# adc_chanels.net
KiCad netlist of a schematic drawn in Altium Designer
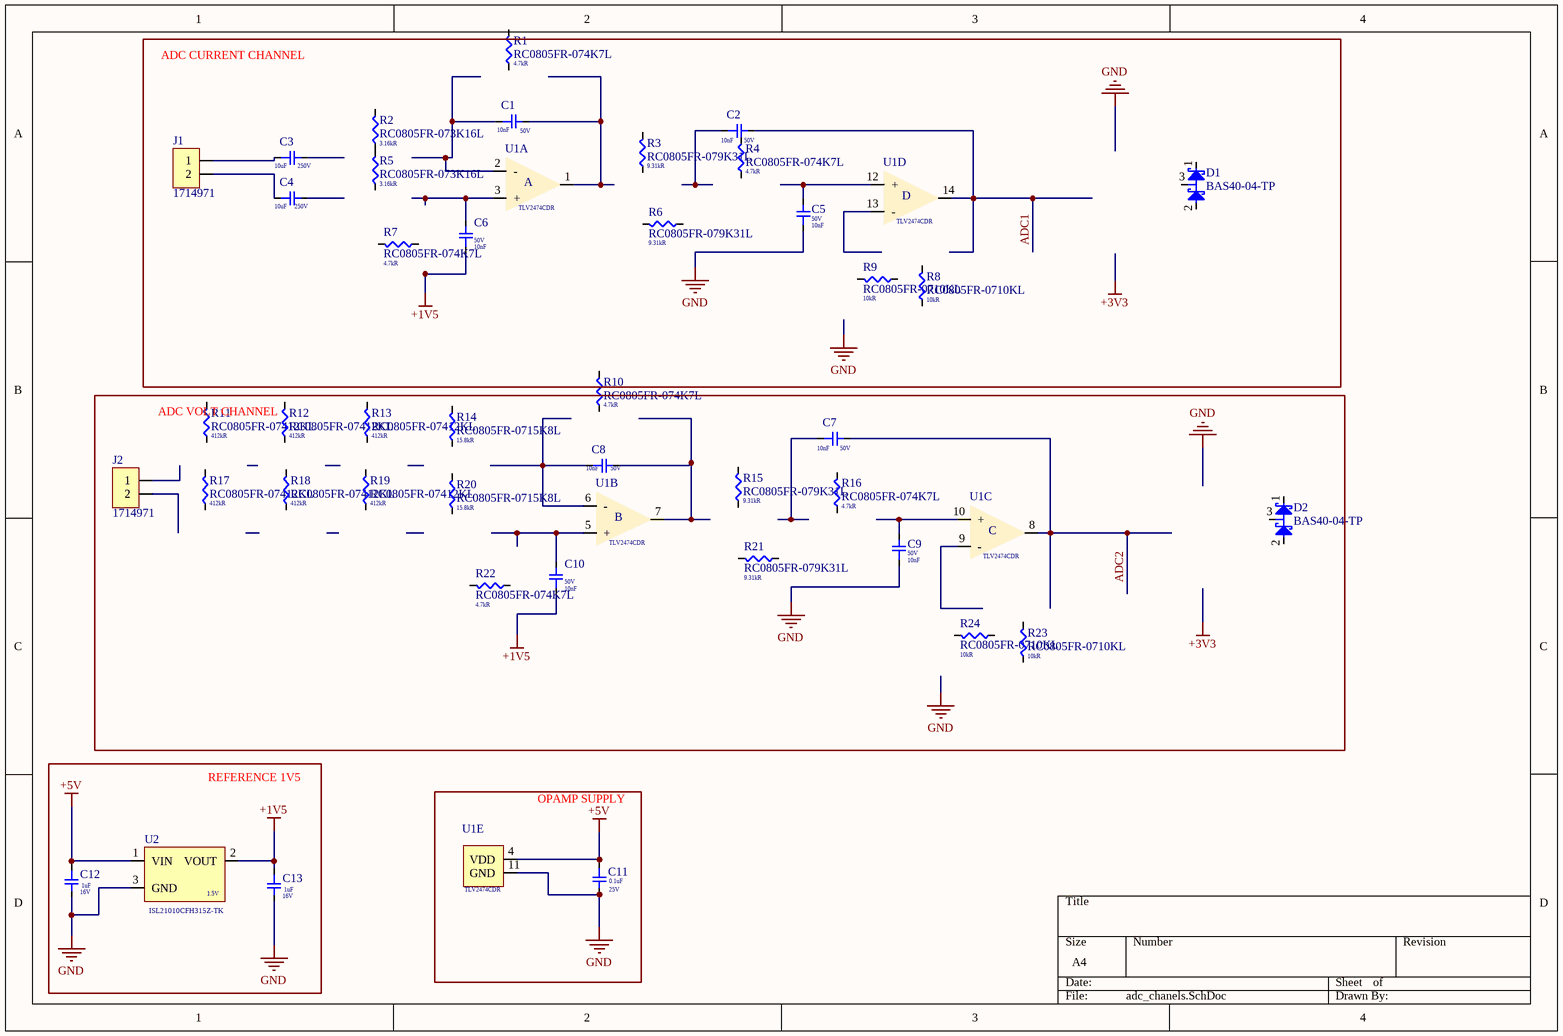
[diagram p0: adc_chanels.SchDoc]

(export (version "E")
  (design (tool "Eeschema 10.0.6"))
  (components
    (comp (ref "C1")
      (value "CAP_GRM2195C1H103FA01D_MURATA")
      (footprint "CAP smd 0805")
      (description "0805 10 nF 50 V ±1% Tolerance C0G SMD Multilayer Ceramic Capacitor")
      (fields
        (field (name "TOLERANCE") "1%")
        (field (name "VOLTAGE") "50V")
        (field (name "CAPACITANCE") "10nF")
      )
      (libsource (lib "Cap") (part "CAP_GRM2195C1H103FA01D_MURATA"))
    )
    (comp (ref "C2")
      (value "CAP_GRM2195C1H103FA01D_MURATA")
      (footprint "CAP smd 0805")
      (description "0805 10 nF 50 V ±1% Tolerance C0G SMD Multilayer Ceramic Capacitor")
      (fields
        (field (name "TOLERANCE") "1%")
        (field (name "VOLTAGE") "50V")
        (field (name "CAPACITANCE") "10nF")
      )
      (libsource (lib "Cap") (part "CAP_GRM2195C1H103FA01D_MURATA"))
    )
    (comp (ref "C3")
      (value "CAP_B32754C2106K000")
      (footprint "Cap 22x36.5x31.5")
      (description "Cap Film 10uF 500V PP 10% (31.5 X 22 X 36.5mm) Dipped Radial 27.5mm 105°C Bulk")
      (fields
        (field (name "TOLERANCE") "10%")
        (field (name "VOLTAGE RATING (AC)") "250V")
        (field (name "CAPACITANCE") "10uF")
      )
      (libsource (lib "Cap") (part "CAP_B32754C2106K000"))
    )
    (comp (ref "C4")
      (value "CAP_B32754C2106K000")
      (footprint "Cap 22x36.5x31.5")
      (description "Cap Film 10uF 500V PP 10% (31.5 X 22 X 36.5mm) Dipped Radial 27.5mm 105°C Bulk")
      (fields
        (field (name "TOLERANCE") "10%")
        (field (name "VOLTAGE RATING (AC)") "250V")
        (field (name "CAPACITANCE") "10uF")
      )
      (libsource (lib "Cap") (part "CAP_B32754C2106K000"))
    )
    (comp (ref "C5")
      (value "CAP_GRM2195C1H103FA01D_MURATA")
      (footprint "CAP smd 0805")
      (description "0805 10 nF 50 V ±1% Tolerance C0G SMD Multilayer Ceramic Capacitor")
      (fields
        (field (name "TOLERANCE") "1%")
        (field (name "VOLTAGE") "50V")
        (field (name "CAPACITANCE") "10nF")
      )
      (libsource (lib "Cap") (part "CAP_GRM2195C1H103FA01D_MURATA"))
    )
    (comp (ref "C6")
      (value "CAP_GRM2195C1H103FA01D_MURATA")
      (footprint "CAP smd 0805")
      (description "0805 10 nF 50 V ±1% Tolerance C0G SMD Multilayer Ceramic Capacitor")
      (fields
        (field (name "TOLERANCE") "1%")
        (field (name "VOLTAGE") "50V")
        (field (name "CAPACITANCE") "10nF")
      )
      (libsource (lib "Cap") (part "CAP_GRM2195C1H103FA01D_MURATA"))
    )
    (comp (ref "C7")
      (value "CAP_GRM2195C1H103FA01D_MURATA")
      (footprint "CAP smd 0805")
      (description "0805 10 nF 50 V ±1% Tolerance C0G SMD Multilayer Ceramic Capacitor")
      (fields
        (field (name "TOLERANCE") "1%")
        (field (name "VOLTAGE") "50V")
        (field (name "CAPACITANCE") "10nF")
      )
      (libsource (lib "Cap") (part "CAP_GRM2195C1H103FA01D_MURATA"))
    )
    (comp (ref "C8")
      (value "CAP_GRM2195C1H103FA01D_MURATA")
      (footprint "CAP smd 0805")
      (description "0805 10 nF 50 V ±1% Tolerance C0G SMD Multilayer Ceramic Capacitor")
      (fields
        (field (name "TOLERANCE") "1%")
        (field (name "VOLTAGE") "50V")
        (field (name "CAPACITANCE") "10nF")
      )
      (libsource (lib "Cap") (part "CAP_GRM2195C1H103FA01D_MURATA"))
    )
    (comp (ref "C9")
      (value "CAP_GRM2195C1H103FA01D_MURATA")
      (footprint "CAP smd 0805")
      (description "0805 10 nF 50 V ±1% Tolerance C0G SMD Multilayer Ceramic Capacitor")
      (fields
        (field (name "TOLERANCE") "1%")
        (field (name "VOLTAGE") "50V")
        (field (name "CAPACITANCE") "10nF")
      )
      (libsource (lib "Cap") (part "CAP_GRM2195C1H103FA01D_MURATA"))
    )
    (comp (ref "C10")
      (value "CAP_GRM2195C1H103FA01D_MURATA")
      (footprint "CAP smd 0805")
      (description "0805 10 nF 50 V ±1% Tolerance C0G SMD Multilayer Ceramic Capacitor")
      (fields
        (field (name "TOLERANCE") "1%")
        (field (name "VOLTAGE") "50V")
        (field (name "CAPACITANCE") "10nF")
      )
      (libsource (lib "Cap") (part "CAP_GRM2195C1H103FA01D_MURATA"))
    )
    (comp (ref "C11")
      (value "CAP_CC0805KRX7R8BB104_YAGEO")
      (footprint "CAP smd 0805")
      (description "CAPACITOR, 0805, 100NF, 25V, REEL 4000")
      (fields
        (field (name "TOLERANCE") "10%")
        (field (name "VOLTAGE RATING") "25V")
        (field (name "CAPACITANCE") "0.1uF")
      )
      (libsource (lib "Cap") (part "CAP_CC0805KRX7R8BB104_YAGEO"))
    )
    (comp (ref "C12")
      (value "CAP_CC0805KKX7R7BB105_YAGEO")
      (footprint "CAP smd 0805")
      (description "YAGEO   CC0805KKX7R7BB105   CERAMIC CAPACITOR, 1UF, 16V, X7R, 10%, 0805")
      (fields
        (field (name "TOLERANCE") "10%")
        (field (name "VOLTAGE RATING") "16V")
        (field (name "CAPACITANCE") "1uF")
      )
      (libsource (lib "Cap") (part "CAP_CC0805KKX7R7BB105_YAGEO"))
    )
    (comp (ref "C13")
      (value "CAP_CC0805KKX7R7BB105_YAGEO")
      (footprint "CAP smd 0805")
      (description "YAGEO   CC0805KKX7R7BB105   CERAMIC CAPACITOR, 1UF, 16V, X7R, 10%, 0805")
      (fields
        (field (name "TOLERANCE") "10%")
        (field (name "VOLTAGE RATING") "16V")
        (field (name "CAPACITANCE") "1uF")
      )
      (libsource (lib "Cap") (part "CAP_CC0805KKX7R7BB105_YAGEO"))
    )
    (comp (ref "D1")
      (value "BAS40-04-TP")
      (footprint "SOT-23")
      (description "DIODE ARRAY SCHOTTKY 40V SOT23")
      (libsource (lib "diode") (part "BAS40-04-TP"))
    )
    (comp (ref "D2")
      (value "BAS40-04-TP")
      (footprint "SOT-23")
      (description "DIODE ARRAY SCHOTTKY 40V SOT23")
      (libsource (lib "diode") (part "BAS40-04-TP"))
    )
    (comp (ref "J1")
      (value "1714971")
      (description "Large Style 2pos 32a 500vac 24-10awg Green Plastic Interlocking Housing 9.5.0mm Pitch")
      (fields (field (name "VOLTAGE") "600V"))
      (libsource (lib "conectors") (part "1714971"))
    )
    (comp (ref "J2")
      (value "1714971")
      (description "Large Style 2pos 32a 500vac 24-10awg Green Plastic Interlocking Housing 9.5.0mm Pitch")
      (fields (field (name "VOLTAGE") "600V"))
      (libsource (lib "conectors") (part "1714971"))
    )
    (comp (ref "R1")
      (value "RC0805FR-074K7L")
      (footprint "res 0805")
      (description "YAGEO - RC0805FR-074K7L - SMD  0805 [2012 Metric], 4.7 kohm,  125 mW")
      (fields (field (name "TOLERANCE") "1%") (field (name "RESISTANCE") "4.7kR"))
      (libsource (lib "res") (part "RC0805FR-074K7L"))
    )
    (comp (ref "R2")
      (value "RC0805FR-073K16L")
      (footprint "res 0805")
      (description "Res Thick Film smd 0805 3.16K Ohm 1% 0.125W(1/8W)")
      (fields (field (name "TOLERANCE") "1%") (field (name "RESISTANCE") "3.16kR"))
      (libsource (lib "res") (part "RC0805FR-073K16L"))
    )
    (comp (ref "R3")
      (value "RC0805FR-079K31L")
      (footprint "res 0805")
      (description "Res Thick Film smd 0805 9.31K Ohm 1% 0.125W(1/8W)")
      (fields (field (name "TOLERANCE") "1%") (field (name "RESISTANCE") "9.31kR"))
      (libsource (lib "res") (part "RC0805FR-079K31L"))
    )
    (comp (ref "R4")
      (value "RC0805FR-074K7L")
      (footprint "res 0805")
      (description "YAGEO - RC0805FR-074K7L - SMD  0805 [2012 Metric], 4.7 kohm,  125 mW")
      (fields (field (name "TOLERANCE") "1%") (field (name "RESISTANCE") "4.7kR"))
      (libsource (lib "res") (part "RC0805FR-074K7L"))
    )
    (comp (ref "R5")
      (value "RC0805FR-073K16L")
      (footprint "res 0805")
      (description "Res Thick Film smd 0805 3.16K Ohm 1% 0.125W(1/8W)")
      (fields (field (name "TOLERANCE") "1%") (field (name "RESISTANCE") "3.16kR"))
      (libsource (lib "res") (part "RC0805FR-073K16L"))
    )
    (comp (ref "R6")
      (value "RC0805FR-079K31L")
      (footprint "res 0805")
      (description "Res Thick Film smd 0805 9.31K Ohm 1% 0.125W(1/8W)")
      (fields (field (name "TOLERANCE") "1%") (field (name "RESISTANCE") "9.31kR"))
      (libsource (lib "res") (part "RC0805FR-079K31L"))
    )
    (comp (ref "R7")
      (value "RC0805FR-074K7L")
      (footprint "res 0805")
      (description "YAGEO - RC0805FR-074K7L - SMD  0805 [2012 Metric], 4.7 kohm,  125 mW")
      (fields (field (name "TOLERANCE") "1%") (field (name "RESISTANCE") "4.7kR"))
      (libsource (lib "res") (part "RC0805FR-074K7L"))
    )
    (comp (ref "R8")
      (value "RC0805FR-0710KL")
      (footprint "res 0805")
      (description "RES SMD  0805 10K OHM 1% 1/8W")
      (fields (field (name "TOLERANCE") "1%") (field (name "RESISTANCE") "10kR"))
      (libsource (lib "res") (part "RC0805FR-0710KL"))
    )
    (comp (ref "R9")
      (value "RC0805FR-0710KL")
      (footprint "res 0805")
      (description "RES SMD  0805 10K OHM 1% 1/8W")
      (fields (field (name "TOLERANCE") "1%") (field (name "RESISTANCE") "10kR"))
      (libsource (lib "res") (part "RC0805FR-0710KL"))
    )
    (comp (ref "R10")
      (value "RC0805FR-074K7L")
      (footprint "res 0805")
      (description "YAGEO - RC0805FR-074K7L - SMD  0805 [2012 Metric], 4.7 kohm,  125 mW")
      (fields (field (name "TOLERANCE") "1%") (field (name "RESISTANCE") "4.7kR"))
      (libsource (lib "res") (part "RC0805FR-074K7L"))
    )
    (comp (ref "R11")
      (value "RC0805FR-07412KL")
      (footprint "res 0805")
      (description "RES SMD 0805 412K OHM 1% 1/8W")
      (fields (field (name "TOLERANCE") "1%") (field (name "RESISTANCE") "412kR"))
      (libsource (lib "res") (part "RC0805FR-07412KL"))
    )
    (comp (ref "R12")
      (value "RC0805FR-07412KL")
      (footprint "res 0805")
      (description "RES SMD 0805 412K OHM 1% 1/8W")
      (fields (field (name "TOLERANCE") "1%") (field (name "RESISTANCE") "412kR"))
      (libsource (lib "res") (part "RC0805FR-07412KL"))
    )
    (comp (ref "R13")
      (value "RC0805FR-07412KL")
      (footprint "res 0805")
      (description "RES SMD 0805 412K OHM 1% 1/8W")
      (fields (field (name "TOLERANCE") "1%") (field (name "RESISTANCE") "412kR"))
      (libsource (lib "res") (part "RC0805FR-07412KL"))
    )
    (comp (ref "R14")
      (value "RC0805FR-0715K8L")
      (footprint "res 0805")
      (description "Res Thick Film smd 0805 15.8K Ohm 1% 0.125W(1/8W)")
      (fields (field (name "TOLERANCE") "1%") (field (name "RESISTANCE") "15.8kR"))
      (libsource (lib "res") (part "RC0805FR-0715K8L"))
    )
    (comp (ref "R15")
      (value "RC0805FR-079K31L")
      (footprint "res 0805")
      (description "Res Thick Film smd 0805 9.31K Ohm 1% 0.125W(1/8W)")
      (fields (field (name "TOLERANCE") "1%") (field (name "RESISTANCE") "9.31kR"))
      (libsource (lib "res") (part "RC0805FR-079K31L"))
    )
    (comp (ref "R16")
      (value "RC0805FR-074K7L")
      (footprint "res 0805")
      (description "YAGEO - RC0805FR-074K7L - SMD  0805 [2012 Metric], 4.7 kohm,  125 mW")
      (fields (field (name "TOLERANCE") "1%") (field (name "RESISTANCE") "4.7kR"))
      (libsource (lib "res") (part "RC0805FR-074K7L"))
    )
    (comp (ref "R17")
      (value "RC0805FR-07412KL")
      (footprint "res 0805")
      (description "RES SMD 0805 412K OHM 1% 1/8W")
      (fields (field (name "TOLERANCE") "1%") (field (name "RESISTANCE") "412kR"))
      (libsource (lib "res") (part "RC0805FR-07412KL"))
    )
    (comp (ref "R18")
      (value "RC0805FR-07412KL")
      (footprint "res 0805")
      (description "RES SMD 0805 412K OHM 1% 1/8W")
      (fields (field (name "TOLERANCE") "1%") (field (name "RESISTANCE") "412kR"))
      (libsource (lib "res") (part "RC0805FR-07412KL"))
    )
    (comp (ref "R19")
      (value "RC0805FR-07412KL")
      (footprint "res 0805")
      (description "RES SMD 0805 412K OHM 1% 1/8W")
      (fields (field (name "TOLERANCE") "1%") (field (name "RESISTANCE") "412kR"))
      (libsource (lib "res") (part "RC0805FR-07412KL"))
    )
    (comp (ref "R20")
      (value "RC0805FR-0715K8L")
      (footprint "res 0805")
      (description "Res Thick Film smd 0805 15.8K Ohm 1% 0.125W(1/8W)")
      (fields (field (name "TOLERANCE") "1%") (field (name "RESISTANCE") "15.8kR"))
      (libsource (lib "res") (part "RC0805FR-0715K8L"))
    )
    (comp (ref "R21")
      (value "RC0805FR-079K31L")
      (footprint "res 0805")
      (description "Res Thick Film smd 0805 9.31K Ohm 1% 0.125W(1/8W)")
      (fields (field (name "TOLERANCE") "1%") (field (name "RESISTANCE") "9.31kR"))
      (libsource (lib "res") (part "RC0805FR-079K31L"))
    )
    (comp (ref "R22")
      (value "RC0805FR-074K7L")
      (footprint "res 0805")
      (description "YAGEO - RC0805FR-074K7L - SMD  0805 [2012 Metric], 4.7 kohm,  125 mW")
      (fields (field (name "TOLERANCE") "1%") (field (name "RESISTANCE") "4.7kR"))
      (libsource (lib "res") (part "RC0805FR-074K7L"))
    )
    (comp (ref "R23")
      (value "RC0805FR-0710KL")
      (footprint "res 0805")
      (description "RES SMD  0805 10K OHM 1% 1/8W")
      (fields (field (name "TOLERANCE") "1%") (field (name "RESISTANCE") "10kR"))
      (libsource (lib "res") (part "RC0805FR-0710KL"))
    )
    (comp (ref "R24")
      (value "RC0805FR-0710KL")
      (footprint "res 0805")
      (description "RES SMD  0805 10K OHM 1% 1/8W")
      (fields (field (name "TOLERANCE") "1%") (field (name "RESISTANCE") "10kR"))
      (libsource (lib "res") (part "RC0805FR-0710KL"))
    )
    (comp (ref "U1")
      (value "TLV2474CDR")
      (description "OP Amp Quad GP R-R I/O ±3V/6V 14-Pin SOIC T/R")
      (libsource (lib "ic") (part "TLV2474CDR"))
    )
    (comp (ref "U2")
      (value "ISL21010CFH315Z-TK")
      (fields
        (field (name "TOLERANCE") "0.2%")
        (field (name "MANUFACTURER PART NUMBER 1") "ISL21010CFH315Z-TK")
        (field (name "REFERENCE VOLTAGE") "1.5V")
      )
      (libsource (lib "ic") (part "ISL21010CFH315Z-TK"))
    )
  )
  (nets
    (net (code "1") (name "+1V5") (class "Default")
      (node (ref "C10") (pin "23") (pinfunction "23_23") (pintype "passive"))
      (node (ref "C13") (pin "23") (pinfunction "23_23") (pintype "passive"))
      (node (ref "C6") (pin "23") (pinfunction "23_23") (pintype "passive"))
      (node (ref "U2") (pin "2") (pinfunction "VOUT_2") (pintype "passive"))
    )
    (net (code "3") (name "+5V") (class "Default")
      (node (ref "C11") (pin "23") (pinfunction "23_23") (pintype "passive"))
      (node (ref "C12") (pin "23") (pinfunction "23_23") (pintype "passive"))
      (node (ref "U1") (pin "4") (pinfunction "VDD_4") (pintype "passive"))
      (node (ref "U2") (pin "1") (pinfunction "VIN_1") (pintype "passive"))
    )
    (net (code "4") (name "/ADC1") (class "Default")
      (node (ref "C2") (pin "22") (pinfunction "22_22") (pintype "passive"))
      (node (ref "U1") (pin "14") (pinfunction "14_14") (pintype "passive"))
    )
    (net (code "5") (name "/ADC2") (class "Default")
      (node (ref "C7") (pin "22") (pinfunction "22_22") (pintype "passive"))
      (node (ref "U1") (pin "8") (pinfunction "1_8") (pintype "passive"))
    )
    (net (code "6") (name "GND") (class "Default")
      (node (ref "C11") (pin "22") (pinfunction "22_22") (pintype "passive"))
      (node (ref "C12") (pin "22") (pinfunction "22_22") (pintype "passive"))
      (node (ref "C13") (pin "22") (pinfunction "22_22") (pintype "passive"))
      (node (ref "C5") (pin "23") (pinfunction "23_23") (pintype "passive"))
      (node (ref "C9") (pin "23") (pinfunction "23_23") (pintype "passive"))
      (node (ref "U1") (pin "11") (pinfunction "GND_11") (pintype "passive"))
      (node (ref "U2") (pin "3") (pinfunction "GND_3") (pintype "passive"))
    )
    (net (code "7") (name "Net-(C1-Pad22)") (class "Default")
      (node (ref "C1") (pin "22") (pinfunction "22_22") (pintype "passive"))
      (node (ref "U1") (pin "1") (pinfunction "1_1") (pintype "passive"))
    )
    (net (code "8") (name "Net-(C3-Pad23)") (class "Default")
      (node (ref "C3") (pin "23") (pinfunction "23_23") (pintype "passive"))
      (node (ref "J1") (pin "1") (pinfunction "1_1") (pintype "passive"))
    )
    (net (code "9") (name "Net-(C4-Pad23)") (class "Default")
      (node (ref "C4") (pin "23") (pinfunction "23_23") (pintype "passive"))
      (node (ref "J1") (pin "2") (pinfunction "2_2") (pintype "passive"))
    )
    (net (code "10") (name "Net-(R2-Pad2)") (class "Default")
      (node (ref "R2") (pin "2") (pinfunction "2_2") (pintype "passive"))
      (node (ref "R5") (pin "1") (pinfunction "1_1") (pintype "passive"))
    )
    (net (code "11") (name "Net-(U1A-+)") (class "Default")
      (node (ref "C6") (pin "22") (pinfunction "22_22") (pintype "passive"))
      (node (ref "U1") (pin "3") (pinfunction "+_3") (pintype "passive"))
    )
    (net (code "12") (name "Net-(U1A--)") (class "Default")
      (node (ref "C1") (pin "23") (pinfunction "23_23") (pintype "passive"))
      (node (ref "U1") (pin "2") (pinfunction "-_2") (pintype "passive"))
    )
    (net (code "13") (name "Net-(U1B-+)") (class "Default")
      (node (ref "C10") (pin "22") (pinfunction "22_22") (pintype "passive"))
      (node (ref "U1") (pin "5") (pinfunction "+_5") (pintype "passive"))
    )
    (net (code "14") (name "Net-(U1B--)") (class "Default")
      (node (ref "C8") (pin "23") (pinfunction "23_23") (pintype "passive"))
      (node (ref "U1") (pin "6") (pinfunction "-_6") (pintype "passive"))
    )
    (net (code "15") (name "Net-(U1B-1)") (class "Default")
      (node (ref "C8") (pin "22") (pinfunction "22_22") (pintype "passive"))
      (node (ref "U1") (pin "7") (pinfunction "1_7") (pintype "passive"))
    )
    (net (code "16") (name "Net-(U1C-+)") (class "Default")
      (node (ref "C9") (pin "22") (pinfunction "22_22") (pintype "passive"))
      (node (ref "U1") (pin "10") (pinfunction "+_10") (pintype "passive"))
    )
    (net (code "17") (name "Net-(U1D-+)") (class "Default")
      (node (ref "C5") (pin "22") (pinfunction "22_22") (pintype "passive"))
      (node (ref "U1") (pin "12") (pinfunction "+_12") (pintype "passive"))
    )
    (net (code "18") (name "unconnected-(C2-Pad23)") (class "Default")
      (node (ref "C2") (pin "23") (pinfunction "23_23") (pintype "passive"))
    )
    (net (code "19") (name "unconnected-(C3-Pad22)") (class "Default")
      (node (ref "C3") (pin "22") (pinfunction "22_22") (pintype "passive"))
    )
    (net (code "20") (name "unconnected-(C4-Pad22)") (class "Default")
      (node (ref "C4") (pin "22") (pinfunction "22_22") (pintype "passive"))
    )
    (net (code "21") (name "unconnected-(C7-Pad23)") (class "Default")
      (node (ref "C7") (pin "23") (pinfunction "23_23") (pintype "passive"))
    )
    (net (code "22") (name "unconnected-(D1-Pad1)") (class "Default")
      (node (ref "D1") (pin "1") (pinfunction "1_1") (pintype "passive"))
    )
    (net (code "23") (name "unconnected-(D1-Pad2)") (class "Default")
      (node (ref "D1") (pin "2") (pinfunction "2_2") (pintype "passive"))
    )
    (net (code "24") (name "unconnected-(D1-Pad3)") (class "Default")
      (node (ref "D1") (pin "3") (pinfunction "3_3") (pintype "passive"))
    )
    (net (code "25") (name "unconnected-(D2-Pad1)") (class "Default")
      (node (ref "D2") (pin "1") (pinfunction "1_1") (pintype "passive"))
    )
    (net (code "26") (name "unconnected-(D2-Pad2)") (class "Default")
      (node (ref "D2") (pin "2") (pinfunction "2_2") (pintype "passive"))
    )
    (net (code "27") (name "unconnected-(D2-Pad3)") (class "Default")
      (node (ref "D2") (pin "3") (pinfunction "3_3") (pintype "passive"))
    )
    (net (code "28") (name "unconnected-(J2-Pad1)") (class "Default")
      (node (ref "J2") (pin "1") (pinfunction "1_1") (pintype "passive"))
    )
    (net (code "29") (name "unconnected-(J2-Pad2)") (class "Default")
      (node (ref "J2") (pin "2") (pinfunction "2_2") (pintype "passive"))
    )
    (net (code "30") (name "unconnected-(R1-Pad1)") (class "Default")
      (node (ref "R1") (pin "1") (pinfunction "1_1") (pintype "passive"))
    )
    (net (code "31") (name "unconnected-(R1-Pad2)") (class "Default")
      (node (ref "R1") (pin "2") (pinfunction "2_2") (pintype "passive"))
    )
    (net (code "32") (name "unconnected-(R2-Pad1)") (class "Default")
      (node (ref "R2") (pin "1") (pinfunction "1_1") (pintype "passive"))
    )
    (net (code "33") (name "unconnected-(R3-Pad1)") (class "Default")
      (node (ref "R3") (pin "1") (pinfunction "1_1") (pintype "passive"))
    )
    (net (code "34") (name "unconnected-(R3-Pad2)") (class "Default")
      (node (ref "R3") (pin "2") (pinfunction "2_2") (pintype "passive"))
    )
    (net (code "35") (name "unconnected-(R4-Pad1)") (class "Default")
      (node (ref "R4") (pin "1") (pinfunction "1_1") (pintype "passive"))
    )
    (net (code "36") (name "unconnected-(R4-Pad2)") (class "Default")
      (node (ref "R4") (pin "2") (pinfunction "2_2") (pintype "passive"))
    )
    (net (code "37") (name "unconnected-(R5-Pad2)") (class "Default")
      (node (ref "R5") (pin "2") (pinfunction "2_2") (pintype "passive"))
    )
    (net (code "38") (name "unconnected-(R6-Pad1)") (class "Default")
      (node (ref "R6") (pin "1") (pinfunction "1_1") (pintype "passive"))
    )
    (net (code "39") (name "unconnected-(R6-Pad2)") (class "Default")
      (node (ref "R6") (pin "2") (pinfunction "2_2") (pintype "passive"))
    )
    (net (code "40") (name "unconnected-(R7-Pad1)") (class "Default")
      (node (ref "R7") (pin "1") (pinfunction "1_1") (pintype "passive"))
    )
    (net (code "41") (name "unconnected-(R7-Pad2)") (class "Default")
      (node (ref "R7") (pin "2") (pinfunction "2_2") (pintype "passive"))
    )
    (net (code "42") (name "unconnected-(R8-Pad1)") (class "Default")
      (node (ref "R8") (pin "1") (pinfunction "1_1") (pintype "passive"))
    )
    (net (code "43") (name "unconnected-(R8-Pad2)") (class "Default")
      (node (ref "R8") (pin "2") (pinfunction "2_2") (pintype "passive"))
    )
    (net (code "44") (name "unconnected-(R9-Pad1)") (class "Default")
      (node (ref "R9") (pin "1") (pinfunction "1_1") (pintype "passive"))
    )
    (net (code "45") (name "unconnected-(R9-Pad2)") (class "Default")
      (node (ref "R9") (pin "2") (pinfunction "2_2") (pintype "passive"))
    )
    (net (code "46") (name "unconnected-(R10-Pad1)") (class "Default")
      (node (ref "R10") (pin "1") (pinfunction "1_1") (pintype "passive"))
    )
    (net (code "47") (name "unconnected-(R10-Pad2)") (class "Default")
      (node (ref "R10") (pin "2") (pinfunction "2_2") (pintype "passive"))
    )
    (net (code "48") (name "unconnected-(R11-Pad1)") (class "Default")
      (node (ref "R11") (pin "1") (pinfunction "1_1") (pintype "passive"))
    )
    (net (code "49") (name "unconnected-(R11-Pad2)") (class "Default")
      (node (ref "R11") (pin "2") (pinfunction "2_2") (pintype "passive"))
    )
    (net (code "50") (name "unconnected-(R12-Pad1)") (class "Default")
      (node (ref "R12") (pin "1") (pinfunction "1_1") (pintype "passive"))
    )
    (net (code "51") (name "unconnected-(R12-Pad2)") (class "Default")
      (node (ref "R12") (pin "2") (pinfunction "2_2") (pintype "passive"))
    )
    (net (code "52") (name "unconnected-(R13-Pad1)") (class "Default")
      (node (ref "R13") (pin "1") (pinfunction "1_1") (pintype "passive"))
    )
    (net (code "53") (name "unconnected-(R13-Pad2)") (class "Default")
      (node (ref "R13") (pin "2") (pinfunction "2_2") (pintype "passive"))
    )
    (net (code "54") (name "unconnected-(R14-Pad1)") (class "Default")
      (node (ref "R14") (pin "1") (pinfunction "1_1") (pintype "passive"))
    )
    (net (code "55") (name "unconnected-(R14-Pad2)") (class "Default")
      (node (ref "R14") (pin "2") (pinfunction "2_2") (pintype "passive"))
    )
    (net (code "56") (name "unconnected-(R15-Pad1)") (class "Default")
      (node (ref "R15") (pin "1") (pinfunction "1_1") (pintype "passive"))
    )
    (net (code "57") (name "unconnected-(R15-Pad2)") (class "Default")
      (node (ref "R15") (pin "2") (pinfunction "2_2") (pintype "passive"))
    )
    (net (code "58") (name "unconnected-(R16-Pad1)") (class "Default")
      (node (ref "R16") (pin "1") (pinfunction "1_1") (pintype "passive"))
    )
    (net (code "59") (name "unconnected-(R16-Pad2)") (class "Default")
      (node (ref "R16") (pin "2") (pinfunction "2_2") (pintype "passive"))
    )
    (net (code "60") (name "unconnected-(R17-Pad1)") (class "Default")
      (node (ref "R17") (pin "1") (pinfunction "1_1") (pintype "passive"))
    )
    (net (code "61") (name "unconnected-(R17-Pad2)") (class "Default")
      (node (ref "R17") (pin "2") (pinfunction "2_2") (pintype "passive"))
    )
    (net (code "62") (name "unconnected-(R18-Pad1)") (class "Default")
      (node (ref "R18") (pin "1") (pinfunction "1_1") (pintype "passive"))
    )
    (net (code "63") (name "unconnected-(R18-Pad2)") (class "Default")
      (node (ref "R18") (pin "2") (pinfunction "2_2") (pintype "passive"))
    )
    (net (code "64") (name "unconnected-(R19-Pad1)") (class "Default")
      (node (ref "R19") (pin "1") (pinfunction "1_1") (pintype "passive"))
    )
    (net (code "65") (name "unconnected-(R19-Pad2)") (class "Default")
      (node (ref "R19") (pin "2") (pinfunction "2_2") (pintype "passive"))
    )
    (net (code "66") (name "unconnected-(R20-Pad1)") (class "Default")
      (node (ref "R20") (pin "1") (pinfunction "1_1") (pintype "passive"))
    )
    (net (code "67") (name "unconnected-(R20-Pad2)") (class "Default")
      (node (ref "R20") (pin "2") (pinfunction "2_2") (pintype "passive"))
    )
    (net (code "68") (name "unconnected-(R21-Pad1)") (class "Default")
      (node (ref "R21") (pin "1") (pinfunction "1_1") (pintype "passive"))
    )
    (net (code "69") (name "unconnected-(R21-Pad2)") (class "Default")
      (node (ref "R21") (pin "2") (pinfunction "2_2") (pintype "passive"))
    )
    (net (code "70") (name "unconnected-(R22-Pad1)") (class "Default")
      (node (ref "R22") (pin "1") (pinfunction "1_1") (pintype "passive"))
    )
    (net (code "71") (name "unconnected-(R22-Pad2)") (class "Default")
      (node (ref "R22") (pin "2") (pinfunction "2_2") (pintype "passive"))
    )
    (net (code "72") (name "unconnected-(R23-Pad1)") (class "Default")
      (node (ref "R23") (pin "1") (pinfunction "1_1") (pintype "passive"))
    )
    (net (code "73") (name "unconnected-(R23-Pad2)") (class "Default")
      (node (ref "R23") (pin "2") (pinfunction "2_2") (pintype "passive"))
    )
    (net (code "74") (name "unconnected-(R24-Pad1)") (class "Default")
      (node (ref "R24") (pin "1") (pinfunction "1_1") (pintype "passive"))
    )
    (net (code "75") (name "unconnected-(R24-Pad2)") (class "Default")
      (node (ref "R24") (pin "2") (pinfunction "2_2") (pintype "passive"))
    )
    (net (code "76") (name "unconnected-(U1C---Pad9)") (class "Default")
      (node (ref "U1") (pin "9") (pinfunction "-_9") (pintype "passive"))
    )
    (net (code "77") (name "unconnected-(U1D---Pad13)") (class "Default")
      (node (ref "U1") (pin "13") (pinfunction "-_13") (pintype "passive"))
    )
  )
)
